# 77seg_panel_ends.net
KiCad netlist of a schematic drawn in EAGLE
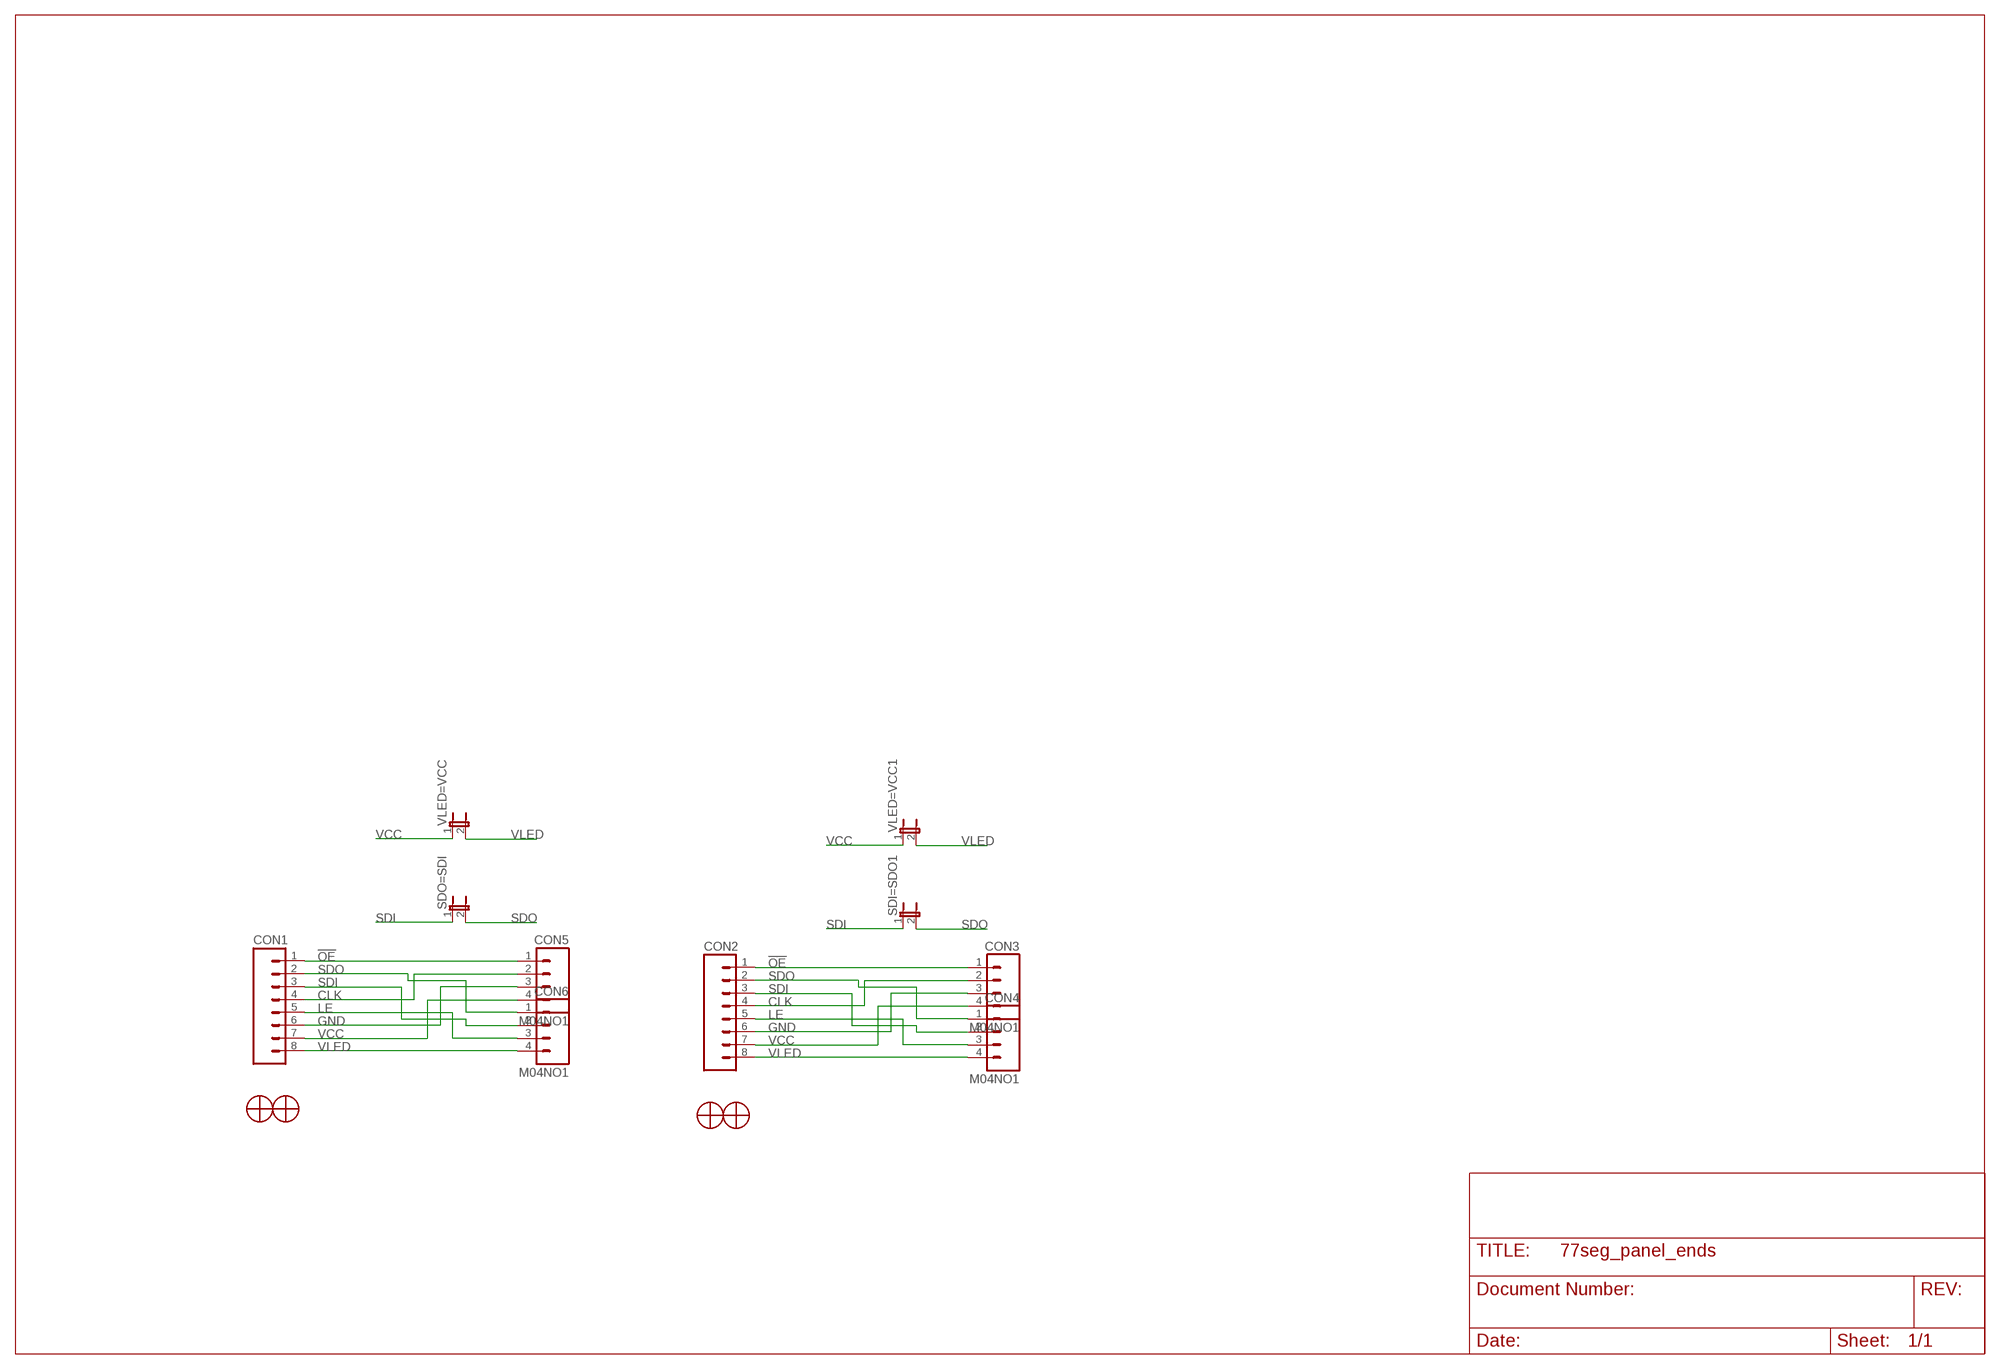
[diagram p0: schematic, sheet 1]

(export (version "E")
  (design (tool "Eeschema 10.0.6"))
  (components
    (comp (ref "CON1")
      (value "M081.27MM_NO1")
      (footprint "eagle-import:1X08_1.27MM_NO1")
      (libsource (lib "eagle-import") (part "M081.27MM_NO1"))
    )
    (comp (ref "CON2")
      (value "M081.27MM_NO1")
      (footprint "eagle-import:1X08_1.27MM_NO1")
      (libsource (lib "eagle-import") (part "M081.27MM_NO1"))
    )
    (comp (ref "CON3")
      (value "M04NO1")
      (footprint "eagle-import:1X04_NO1")
      (libsource (lib "eagle-import") (part "M04NO1"))
    )
    (comp (ref "CON4")
      (value "M04NO1")
      (footprint "eagle-import:1X04_NO1")
      (libsource (lib "eagle-import") (part "M04NO1"))
    )
    (comp (ref "CON5")
      (value "M04NO1")
      (footprint "eagle-import:1X04_NO1")
      (libsource (lib "eagle-import") (part "M04NO1"))
    )
    (comp (ref "CON6")
      (value "M04NO1")
      (footprint "eagle-import:1X04_NO1")
      (libsource (lib "eagle-import") (part "M04NO1"))
    )
    (comp (ref "SDI=SDO1")
      (value "JUMPER-2SMD-NO")
      (footprint "eagle-import:SJ_2S-NO")
      (libsource (lib "eagle-import") (part "JUMPER-2SMD-NO"))
    )
    (comp (ref "SDO=SDI")
      (value "JUMPER-2SMD-NO")
      (footprint "eagle-import:SJ_2S-NO")
      (libsource (lib "eagle-import") (part "JUMPER-2SMD-NO"))
    )
    (comp (ref "U$1")
      (value "SCREW_NOGNDM3_REDUCED")
      (footprint "eagle-import:SCREW_M3_REDUCED")
      (libsource (lib "eagle-import") (part "SCREW_NOGNDM3_REDUCED"))
    )
    (comp (ref "U$2")
      (value "SCREW_NOGNDM3_REDUCED")
      (footprint "eagle-import:SCREW_M3_REDUCED")
      (libsource (lib "eagle-import") (part "SCREW_NOGNDM3_REDUCED"))
    )
    (comp (ref "U$3")
      (value "SCREW_NOGNDM3_REDUCED")
      (footprint "eagle-import:SCREW_M3_REDUCED")
      (libsource (lib "eagle-import") (part "SCREW_NOGNDM3_REDUCED"))
    )
    (comp (ref "U$4")
      (value "SCREW_NOGNDM3_REDUCED")
      (footprint "eagle-import:SCREW_M3_REDUCED")
      (libsource (lib "eagle-import") (part "SCREW_NOGNDM3_REDUCED"))
    )
    (comp (ref "VLED=VCC")
      (value "JUMPER-2SMD-NO")
      (footprint "eagle-import:SJ_2S-NO")
      (libsource (lib "eagle-import") (part "JUMPER-2SMD-NO"))
    )
    (comp (ref "VLED=VCC1")
      (value "JUMPER-2SMD-NO")
      (footprint "eagle-import:SJ_2S-NO")
      (libsource (lib "eagle-import") (part "JUMPER-2SMD-NO"))
    )
  )
  (nets
    (net (code "1") (name "/CLK") (class "Default")
      (node (ref "CON1") (pin "4") (pinfunction "4_4") (pintype "passive"))
      (node (ref "CON2") (pin "4") (pinfunction "4_4") (pintype "passive"))
      (node (ref "CON3") (pin "2") (pinfunction "2_2") (pintype "passive"))
      (node (ref "CON5") (pin "2") (pinfunction "2_2") (pintype "passive"))
    )
    (net (code "2") (name "/GND") (class "Default")
      (node (ref "CON1") (pin "6") (pinfunction "6_6") (pintype "passive"))
      (node (ref "CON2") (pin "6") (pinfunction "6_6") (pintype "passive"))
      (node (ref "CON3") (pin "3") (pinfunction "3_3") (pintype "passive"))
      (node (ref "CON5") (pin "3") (pinfunction "3_3") (pintype "passive"))
    )
    (net (code "3") (name "/LE") (class "Default")
      (node (ref "CON1") (pin "5") (pinfunction "5_5") (pintype "passive"))
      (node (ref "CON2") (pin "5") (pinfunction "5_5") (pintype "passive"))
      (node (ref "CON4") (pin "3") (pinfunction "3_3") (pintype "passive"))
      (node (ref "CON6") (pin "3") (pinfunction "3_3") (pintype "passive"))
    )
    (net (code "4") (name "/SDI") (class "Default")
      (node (ref "CON1") (pin "3") (pinfunction "3_3") (pintype "passive"))
      (node (ref "CON2") (pin "3") (pinfunction "3_3") (pintype "passive"))
      (node (ref "CON4") (pin "2") (pinfunction "2_2") (pintype "passive"))
      (node (ref "CON6") (pin "2") (pinfunction "2_2") (pintype "passive"))
      (node (ref "SDI=SDO1") (pin "1") (pinfunction "1_1") (pintype "passive"))
      (node (ref "SDO=SDI") (pin "1") (pinfunction "1_1") (pintype "passive"))
    )
    (net (code "5") (name "/SDO") (class "Default")
      (node (ref "CON1") (pin "2") (pinfunction "2_2") (pintype "passive"))
      (node (ref "CON2") (pin "2") (pinfunction "2_2") (pintype "passive"))
      (node (ref "CON4") (pin "1") (pinfunction "1_1") (pintype "passive"))
      (node (ref "CON6") (pin "1") (pinfunction "1_1") (pintype "passive"))
      (node (ref "SDI=SDO1") (pin "2") (pinfunction "2_2") (pintype "passive"))
      (node (ref "SDO=SDI") (pin "2") (pinfunction "2_2") (pintype "passive"))
    )
    (net (code "6") (name "/VCC") (class "Default")
      (node (ref "CON1") (pin "7") (pinfunction "7_7") (pintype "passive"))
      (node (ref "CON2") (pin "7") (pinfunction "7_7") (pintype "passive"))
      (node (ref "CON3") (pin "4") (pinfunction "4_4") (pintype "passive"))
      (node (ref "CON5") (pin "4") (pinfunction "4_4") (pintype "passive"))
      (node (ref "VLED=VCC") (pin "1") (pinfunction "1_1") (pintype "passive"))
      (node (ref "VLED=VCC1") (pin "1") (pinfunction "1_1") (pintype "passive"))
    )
    (net (code "7") (name "/VLED") (class "Default")
      (node (ref "CON1") (pin "8") (pinfunction "8_8") (pintype "passive"))
      (node (ref "CON2") (pin "8") (pinfunction "8_8") (pintype "passive"))
      (node (ref "CON4") (pin "4") (pinfunction "4_4") (pintype "passive"))
      (node (ref "CON6") (pin "4") (pinfunction "4_4") (pintype "passive"))
      (node (ref "VLED=VCC") (pin "2") (pinfunction "2_2") (pintype "passive"))
      (node (ref "VLED=VCC1") (pin "2") (pinfunction "2_2") (pintype "passive"))
    )
    (net (code "8") (name "/~{OE}") (class "Default")
      (node (ref "CON1") (pin "1") (pinfunction "1_1") (pintype "passive"))
      (node (ref "CON2") (pin "1") (pinfunction "1_1") (pintype "passive"))
      (node (ref "CON3") (pin "1") (pinfunction "1_1") (pintype "passive"))
      (node (ref "CON5") (pin "1") (pinfunction "1_1") (pintype "passive"))
    )
  )
)
